# Udoo_Shield.net
KiCad netlist of a schematic drawn in EAGLE
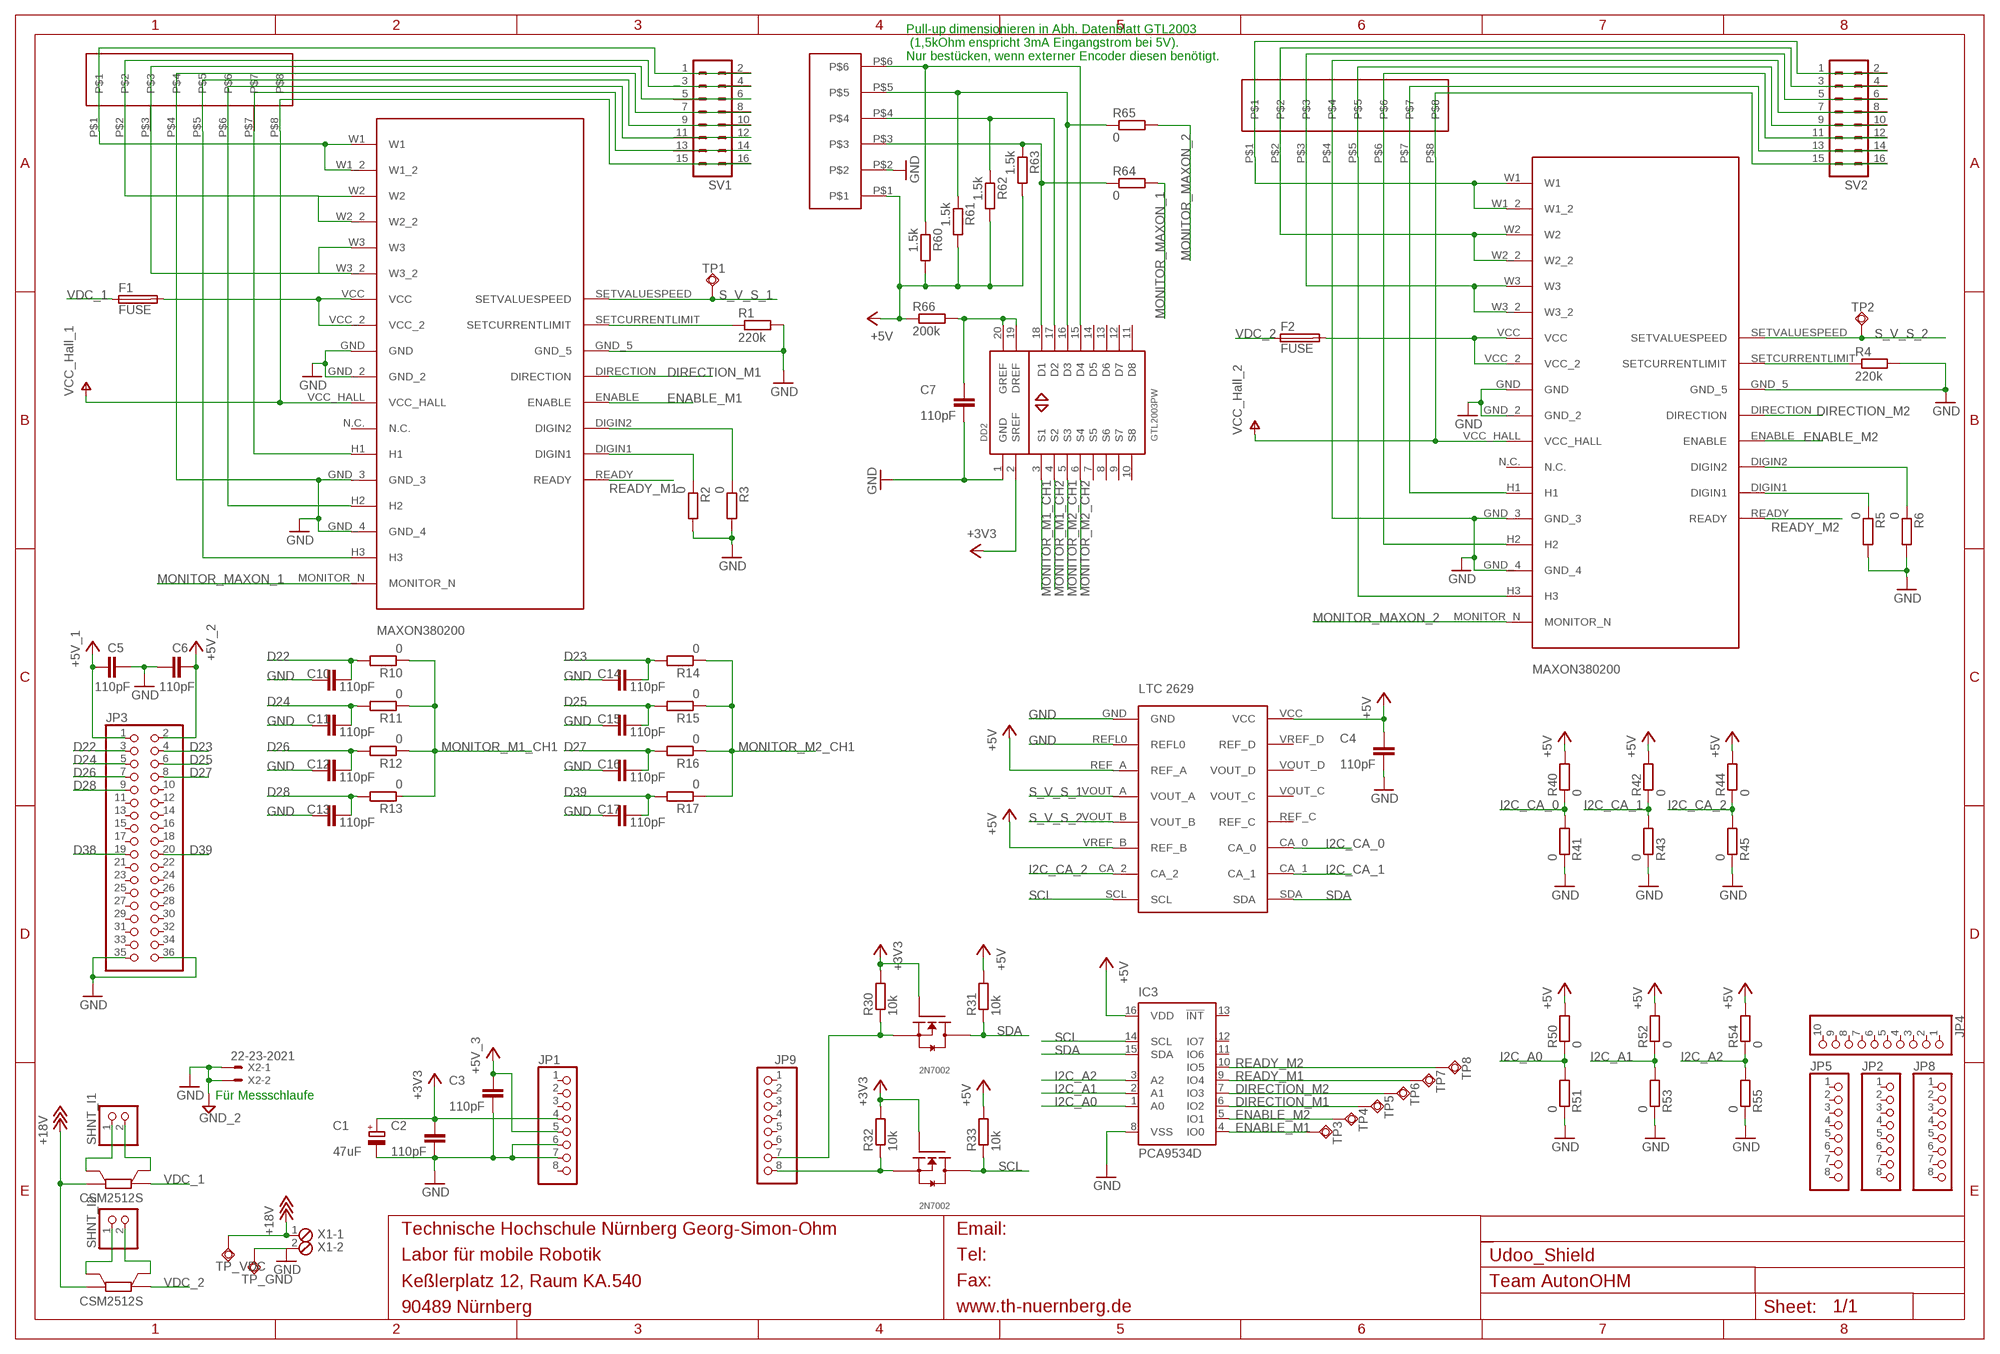
[diagram p0: schematic, sheet 1]

(export (version "E")
  (design (tool "Eeschema 10.0.6"))
  (components
    (comp (ref "C1")
      (value "47uF")
      (footprint "eagle-import:PANASONIC_F")
      (libsource (lib "eagle-import") (part "PANASONI_F_FP"))
    )
    (comp (ref "C2")
      (value "110pF")
      (footprint "eagle-import:SMD-0805")
      (libsource (lib "eagle-import") (part "C-EU0805"))
    )
    (comp (ref "C3")
      (value "110pF")
      (footprint "eagle-import:SMD-0805")
      (libsource (lib "eagle-import") (part "C-EU0805"))
    )
    (comp (ref "C4")
      (value "110pF")
      (footprint "eagle-import:SMD-0805")
      (libsource (lib "eagle-import") (part "C-EU0805"))
    )
    (comp (ref "C5")
      (value "110pF")
      (footprint "eagle-import:SMD-0805")
      (libsource (lib "eagle-import") (part "C-EU0805"))
    )
    (comp (ref "C6")
      (value "110pF")
      (footprint "eagle-import:SMD-0805")
      (libsource (lib "eagle-import") (part "C-EU0805"))
    )
    (comp (ref "C7")
      (value "110pF")
      (footprint "eagle-import:SMD-0805")
      (libsource (lib "eagle-import") (part "C-EU0805"))
    )
    (comp (ref "C10")
      (value "110pF")
      (footprint "eagle-import:SMD-0805")
      (libsource (lib "eagle-import") (part "C-EU0805"))
    )
    (comp (ref "C11")
      (value "110pF")
      (footprint "eagle-import:SMD-0805")
      (libsource (lib "eagle-import") (part "C-EU0805"))
    )
    (comp (ref "C12")
      (value "110pF")
      (footprint "eagle-import:SMD-0805")
      (libsource (lib "eagle-import") (part "C-EU0805"))
    )
    (comp (ref "C13")
      (value "110pF")
      (footprint "eagle-import:SMD-0805")
      (libsource (lib "eagle-import") (part "C-EU0805"))
    )
    (comp (ref "C14")
      (value "110pF")
      (footprint "eagle-import:SMD-0805")
      (libsource (lib "eagle-import") (part "C-EU0805"))
    )
    (comp (ref "C15")
      (value "110pF")
      (footprint "eagle-import:SMD-0805")
      (libsource (lib "eagle-import") (part "C-EU0805"))
    )
    (comp (ref "C16")
      (value "110pF")
      (footprint "eagle-import:SMD-0805")
      (libsource (lib "eagle-import") (part "C-EU0805"))
    )
    (comp (ref "C17")
      (value "110pF")
      (footprint "eagle-import:SMD-0805")
      (libsource (lib "eagle-import") (part "C-EU0805"))
    )
    (comp (ref "DD2")
      (value "GTL2003PW")
      (footprint "eagle-import:TSSOP20")
      (libsource (lib "eagle-import") (part "GTL2003PW"))
    )
    (comp (ref "ENCODER")
      (value "WAGO_PICOMAX_35_6POLIG")
      (footprint "eagle-import:WAGO_PICOMAX_35_6POLIG")
      (libsource (lib "eagle-import") (part "WAGO_PICOMAX_35_6POLIG"))
    )
    (comp (ref "F1")
      (value "FUSE")
      (footprint "eagle-import:FUSE")
      (libsource (lib "eagle-import") (part "FUSE"))
    )
    (comp (ref "F2")
      (value "FUSE")
      (footprint "eagle-import:FUSE")
      (libsource (lib "eagle-import") (part "FUSE"))
    )
    (comp (ref "FRAME1")
      (value "A3L-LOC")
      (footprint "eagle-import:A3L-LOC")
      (fields
        (field (name "AUTHOR") "Team AutonOHM")
        (field (name "PROJECT_NAME") "MaxonShield")
        (field (name "EMAIL") "stefan.may@th-nuernberg.de")
      )
      (libsource (lib "eagle-import") (part "A3L-LOC"))
    )
    (comp (ref "IC3")
      (value "PCA9534D")
      (footprint "eagle-import:SO16W")
      (fields (field (name "MPN") "PCA9534DB"))
      (libsource (lib "eagle-import") (part "PCA9534D"))
    )
    (comp (ref "JP1")
      (value "PINHD-1X8")
      (footprint "eagle-import:1X08")
      (libsource (lib "eagle-import") (part "PINHD-1X8"))
    )
    (comp (ref "JP2")
      (value "PINHD-1X8")
      (footprint "eagle-import:1X08")
      (libsource (lib "eagle-import") (part "PINHD-1X8"))
    )
    (comp (ref "JP3")
      (value "PINHD-2X18")
      (footprint "eagle-import:2X18")
      (libsource (lib "eagle-import") (part "PINHD-2X18"))
    )
    (comp (ref "JP4")
      (value "PINHD-1X10")
      (footprint "eagle-import:1X10")
      (libsource (lib "eagle-import") (part "PINHD-1X10"))
    )
    (comp (ref "JP5")
      (value "PINHD-1X8")
      (footprint "eagle-import:1X08")
      (libsource (lib "eagle-import") (part "PINHD-1X8"))
    )
    (comp (ref "JP8")
      (value "PINHD-1X8")
      (footprint "eagle-import:1X08")
      (libsource (lib "eagle-import") (part "PINHD-1X8"))
    )
    (comp (ref "JP9")
      (value "PINHD-1X8")
      (footprint "eagle-import:1X08")
      (libsource (lib "eagle-import") (part "PINHD-1X8"))
    )
    (comp (ref "R1")
      (value "220k")
      (footprint "eagle-import:M1206")
      (libsource (lib "eagle-import") (part "R-EU_M1206"))
    )
    (comp (ref "R2")
      (value "0")
      (footprint "eagle-import:M0805")
      (libsource (lib "eagle-import") (part "R-EU_M0805"))
    )
    (comp (ref "R3")
      (value "0")
      (footprint "eagle-import:M0805")
      (libsource (lib "eagle-import") (part "R-EU_M0805"))
    )
    (comp (ref "R4")
      (value "220k")
      (footprint "eagle-import:M1206")
      (libsource (lib "eagle-import") (part "R-EU_M1206"))
    )
    (comp (ref "R5")
      (value "0")
      (footprint "eagle-import:M0805")
      (libsource (lib "eagle-import") (part "R-EU_M0805"))
    )
    (comp (ref "R6")
      (value "0")
      (footprint "eagle-import:M0805")
      (libsource (lib "eagle-import") (part "R-EU_M0805"))
    )
    (comp (ref "R10")
      (value "0")
      (footprint "eagle-import:M0805")
      (libsource (lib "eagle-import") (part "R-EU_M0805"))
    )
    (comp (ref "R11")
      (value "0")
      (footprint "eagle-import:M0805")
      (libsource (lib "eagle-import") (part "R-EU_M0805"))
    )
    (comp (ref "R12")
      (value "0")
      (footprint "eagle-import:M0805")
      (libsource (lib "eagle-import") (part "R-EU_M0805"))
    )
    (comp (ref "R13")
      (value "0")
      (footprint "eagle-import:M0805")
      (libsource (lib "eagle-import") (part "R-EU_M0805"))
    )
    (comp (ref "R14")
      (value "0")
      (footprint "eagle-import:M0805")
      (libsource (lib "eagle-import") (part "R-EU_M0805"))
    )
    (comp (ref "R15")
      (value "0")
      (footprint "eagle-import:M0805")
      (libsource (lib "eagle-import") (part "R-EU_M0805"))
    )
    (comp (ref "R16")
      (value "0")
      (footprint "eagle-import:M0805")
      (libsource (lib "eagle-import") (part "R-EU_M0805"))
    )
    (comp (ref "R17")
      (value "0")
      (footprint "eagle-import:M0805")
      (libsource (lib "eagle-import") (part "R-EU_M0805"))
    )
    (comp (ref "R30")
      (value "10k")
      (footprint "eagle-import:M0805")
      (libsource (lib "eagle-import") (part "R-EU_M0805"))
    )
    (comp (ref "R31")
      (value "10k")
      (footprint "eagle-import:M0805")
      (libsource (lib "eagle-import") (part "R-EU_M0805"))
    )
    (comp (ref "R32")
      (value "10k")
      (footprint "eagle-import:M0805")
      (libsource (lib "eagle-import") (part "R-EU_M0805"))
    )
    (comp (ref "R33")
      (value "10k")
      (footprint "eagle-import:M0805")
      (libsource (lib "eagle-import") (part "R-EU_M0805"))
    )
    (comp (ref "R40")
      (value "0")
      (footprint "eagle-import:M0805")
      (libsource (lib "eagle-import") (part "R-EU_M0805"))
    )
    (comp (ref "R41")
      (value "0")
      (footprint "eagle-import:M0805")
      (libsource (lib "eagle-import") (part "R-EU_M0805"))
    )
    (comp (ref "R42")
      (value "0")
      (footprint "eagle-import:M0805")
      (libsource (lib "eagle-import") (part "R-EU_M0805"))
    )
    (comp (ref "R43")
      (value "0")
      (footprint "eagle-import:M0805")
      (libsource (lib "eagle-import") (part "R-EU_M0805"))
    )
    (comp (ref "R44")
      (value "0")
      (footprint "eagle-import:M0805")
      (libsource (lib "eagle-import") (part "R-EU_M0805"))
    )
    (comp (ref "R45")
      (value "0")
      (footprint "eagle-import:M0805")
      (libsource (lib "eagle-import") (part "R-EU_M0805"))
    )
    (comp (ref "R50")
      (value "0")
      (footprint "eagle-import:M0805")
      (libsource (lib "eagle-import") (part "R-EU_M0805"))
    )
    (comp (ref "R51")
      (value "0")
      (footprint "eagle-import:M0805")
      (libsource (lib "eagle-import") (part "R-EU_M0805"))
    )
    (comp (ref "R52")
      (value "0")
      (footprint "eagle-import:M0805")
      (libsource (lib "eagle-import") (part "R-EU_M0805"))
    )
    (comp (ref "R53")
      (value "0")
      (footprint "eagle-import:M0805")
      (libsource (lib "eagle-import") (part "R-EU_M0805"))
    )
    (comp (ref "R54")
      (value "0")
      (footprint "eagle-import:M0805")
      (libsource (lib "eagle-import") (part "R-EU_M0805"))
    )
    (comp (ref "R55")
      (value "0")
      (footprint "eagle-import:M0805")
      (libsource (lib "eagle-import") (part "R-EU_M0805"))
    )
    (comp (ref "R60")
      (value "1.5k")
      (footprint "eagle-import:M0805")
      (libsource (lib "eagle-import") (part "R-EU_M0805"))
    )
    (comp (ref "R61")
      (value "1.5k")
      (footprint "eagle-import:M0805")
      (libsource (lib "eagle-import") (part "R-EU_M0805"))
    )
    (comp (ref "R62")
      (value "1.5k")
      (footprint "eagle-import:M0805")
      (libsource (lib "eagle-import") (part "R-EU_M0805"))
    )
    (comp (ref "R63")
      (value "1.5k")
      (footprint "eagle-import:M0805")
      (libsource (lib "eagle-import") (part "R-EU_M0805"))
    )
    (comp (ref "R64")
      (value "0")
      (footprint "eagle-import:M0805")
      (libsource (lib "eagle-import") (part "R-EU_M0805"))
    )
    (comp (ref "R65")
      (value "0")
      (footprint "eagle-import:M0805")
      (libsource (lib "eagle-import") (part "R-EU_M0805"))
    )
    (comp (ref "R66")
      (value "200k")
      (footprint "eagle-import:M0805")
      (libsource (lib "eagle-import") (part "R-EU_M0805"))
    )
    (comp (ref "SHNT_I1")
      (value "PINHD-1X2")
      (footprint "eagle-import:1X02")
      (libsource (lib "eagle-import") (part "PINHD-1X2"))
    )
    (comp (ref "SHNT_I2")
      (value "PINHD-1X2")
      (footprint "eagle-import:1X02")
      (libsource (lib "eagle-import") (part "PINHD-1X2"))
    )
    (comp (ref "SV1")
      (value "MA08-2")
      (footprint "eagle-import:MA08-2")
      (libsource (lib "eagle-import") (part "MA08-2"))
    )
    (comp (ref "SV2")
      (value "MA08-2")
      (footprint "eagle-import:MA08-2")
      (libsource (lib "eagle-import") (part "MA08-2"))
    )
    (comp (ref "TP1")
      (value "TPSQB1,27")
      (footprint "eagle-import:B1,27")
      (libsource (lib "eagle-import") (part "TPSQB1,27"))
    )
    (comp (ref "TP2")
      (value "TPSQB1,27")
      (footprint "eagle-import:B1,27")
      (libsource (lib "eagle-import") (part "TPSQB1,27"))
    )
    (comp (ref "TP3")
      (value "TPSQB1,27")
      (footprint "eagle-import:B1,27")
      (libsource (lib "eagle-import") (part "TPSQB1,27"))
    )
    (comp (ref "TP4")
      (value "TPSQB1,27")
      (footprint "eagle-import:B1,27")
      (libsource (lib "eagle-import") (part "TPSQB1,27"))
    )
    (comp (ref "TP5")
      (value "TPSQB1,27")
      (footprint "eagle-import:B1,27")
      (libsource (lib "eagle-import") (part "TPSQB1,27"))
    )
    (comp (ref "TP6")
      (value "TPSQB1,27")
      (footprint "eagle-import:B1,27")
      (libsource (lib "eagle-import") (part "TPSQB1,27"))
    )
    (comp (ref "TP7")
      (value "TPSQB1,27")
      (footprint "eagle-import:B1,27")
      (libsource (lib "eagle-import") (part "TPSQB1,27"))
    )
    (comp (ref "TP8")
      (value "TPSQB1,27")
      (footprint "eagle-import:B1,27")
      (libsource (lib "eagle-import") (part "TPSQB1,27"))
    )
    (comp (ref "TP_GND")
      (value "TPSQB1,27")
      (footprint "eagle-import:B1,27")
      (libsource (lib "eagle-import") (part "TPSQB1,27"))
    )
    (comp (ref "TP_VDC")
      (value "TPSQB1,27")
      (footprint "eagle-import:B1,27")
      (libsource (lib "eagle-import") (part "TPSQB1,27"))
    )
    (comp (ref "U$1")
      (value "MAXON380200")
      (footprint "eagle-import:380200")
      (libsource (lib "eagle-import") (part "MAXON380200"))
    )
    (comp (ref "U$2")
      (value "MAXON380200")
      (footprint "eagle-import:380200")
      (libsource (lib "eagle-import") (part "MAXON380200"))
    )
    (comp (ref "U$3")
      (value "WAGO_PICOMAX_35_8POLIG")
      (footprint "eagle-import:WAGO_PICOMAX_35_8POLIG")
      (libsource (lib "eagle-import") (part "WAGO_PICOMAX_35_8POLIG"))
    )
    (comp (ref "U$4")
      (value "WAGO_PICOMAX_35_8POLIG")
      (footprint "eagle-import:WAGO_PICOMAX_35_8POLIG")
      (libsource (lib "eagle-import") (part "WAGO_PICOMAX_35_8POLIG"))
    )
    (comp (ref "U$5")
      (value "LTC2629")
      (footprint "eagle-import:LTC2629")
      (libsource (lib "eagle-import") (part "LTC2629"))
    )
    (comp (ref "U$6")
      (value "N-CH_MOSFET_2N7002")
      (footprint "eagle-import:2N7002")
      (libsource (lib "eagle-import") (part "N-CH_MOSFET_2N7002"))
    )
    (comp (ref "U$10")
      (value "CSM2512S")
      (footprint "eagle-import:CSM2512S")
      (libsource (lib "eagle-import") (part "CSM2512S"))
    )
    (comp (ref "U$14")
      (value "CSM2512S")
      (footprint "eagle-import:CSM2512S")
      (libsource (lib "eagle-import") (part "CSM2512S"))
    )
    (comp (ref "U$15")
      (value "N-CH_MOSFET_2N7002")
      (footprint "eagle-import:2N7002")
      (libsource (lib "eagle-import") (part "N-CH_MOSFET_2N7002"))
    )
    (comp (ref "X1")
      (value "MPT2")
      (footprint "eagle-import:2POL254")
      (libsource (lib "eagle-import") (part "MPT2"))
    )
    (comp (ref "X2")
      (value "22-23-2021")
      (footprint "eagle-import:22-23-2021")
      (fields (field (name "MF") "MOLEX"))
      (libsource (lib "eagle-import") (part "22-23-2021"))
    )
  )
  (nets
    (net (code "1") (name "+3V3") (class "Default")
      (node (ref "C1") (pin "+") (pinfunction "+_+") (pintype "passive"))
      (node (ref "C2") (pin "1") (pinfunction "1_1") (pintype "passive"))
      (node (ref "DD2") (pin "2") (pinfunction "SREF_2") (pintype "input"))
      (node (ref "JP1") (pin "4") (pinfunction "4_4") (pintype "passive"))
      (node (ref "R30") (pin "2") (pinfunction "2_2") (pintype "passive"))
      (node (ref "R32") (pin "2") (pinfunction "2_2") (pintype "passive"))
      (node (ref "U$15") (pin "GATE") (pinfunction "G_GATE") (pintype "passive"))
      (node (ref "U$6") (pin "GATE") (pinfunction "G_GATE") (pintype "passive"))
    )
    (net (code "2") (name "+5V") (class "Default")
      (node (ref "C3") (pin "1") (pinfunction "1_1") (pintype "passive"))
      (node (ref "C4") (pin "1") (pinfunction "1_1") (pintype "passive"))
      (node (ref "C5") (pin "1") (pinfunction "1_1") (pintype "passive"))
      (node (ref "C6") (pin "2") (pinfunction "2_2") (pintype "passive"))
      (node (ref "ENCODER") (pin "P$1") (pinfunction "P$1_P$1") (pintype "bidirectional"))
      (node (ref "IC3") (pin "16") (pinfunction "VDD_16") (pintype "power_in"))
      (node (ref "JP1") (pin "5") (pinfunction "5_5") (pintype "passive"))
      (node (ref "JP3") (pin "1") (pinfunction "1_1") (pintype "passive"))
      (node (ref "JP3") (pin "2") (pinfunction "2_2") (pintype "passive"))
      (node (ref "R31") (pin "2") (pinfunction "2_2") (pintype "passive"))
      (node (ref "R33") (pin "2") (pinfunction "2_2") (pintype "passive"))
      (node (ref "R40") (pin "2") (pinfunction "2_2") (pintype "passive"))
      (node (ref "R42") (pin "2") (pinfunction "2_2") (pintype "passive"))
      (node (ref "R44") (pin "2") (pinfunction "2_2") (pintype "passive"))
      (node (ref "R50") (pin "2") (pinfunction "2_2") (pintype "passive"))
      (node (ref "R52") (pin "2") (pinfunction "2_2") (pintype "passive"))
      (node (ref "R54") (pin "2") (pinfunction "2_2") (pintype "passive"))
      (node (ref "R60") (pin "2") (pinfunction "2_2") (pintype "passive"))
      (node (ref "R61") (pin "2") (pinfunction "2_2") (pintype "passive"))
      (node (ref "R62") (pin "2") (pinfunction "2_2") (pintype "passive"))
      (node (ref "R63") (pin "2") (pinfunction "2_2") (pintype "passive"))
      (node (ref "R66") (pin "1") (pinfunction "1_1") (pintype "passive"))
      (node (ref "U$5") (pin "REF_A") (pinfunction "REF_A_REF_A") (pintype "bidirectional"))
      (node (ref "U$5") (pin "VCC") (pinfunction "VCC_VCC") (pintype "bidirectional"))
      (node (ref "U$5") (pin "VREF_B") (pinfunction "REF_B_VREF_B") (pintype "bidirectional"))
    )
    (net (code "3") (name "+18V") (class "Default")
      (node (ref "TP_VDC") (pin "TP") (pinfunction "TP_TP") (pintype "input"))
      (node (ref "U$10") (pin "I_2") (pinfunction "I_2_I_2") (pintype "passive"))
      (node (ref "U$14") (pin "I_2") (pinfunction "I_2_I_2") (pintype "passive"))
      (node (ref "X1") (pin "1") (pinfunction "1_1") (pintype "passive"))
    )
    (net (code "4") (name "/D22") (class "Default")
      (node (ref "C10") (pin "2") (pinfunction "2_2") (pintype "passive"))
      (node (ref "JP3") (pin "3") (pinfunction "3_3") (pintype "passive"))
      (node (ref "R10") (pin "2") (pinfunction "2_2") (pintype "passive"))
    )
    (net (code "5") (name "/D23") (class "Default")
      (node (ref "C14") (pin "2") (pinfunction "2_2") (pintype "passive"))
      (node (ref "JP3") (pin "4") (pinfunction "4_4") (pintype "passive"))
      (node (ref "R14") (pin "2") (pinfunction "2_2") (pintype "passive"))
    )
    (net (code "6") (name "/D24") (class "Default")
      (node (ref "C11") (pin "2") (pinfunction "2_2") (pintype "passive"))
      (node (ref "JP3") (pin "5") (pinfunction "5_5") (pintype "passive"))
      (node (ref "R11") (pin "2") (pinfunction "2_2") (pintype "passive"))
    )
    (net (code "7") (name "/D25") (class "Default")
      (node (ref "C15") (pin "2") (pinfunction "2_2") (pintype "passive"))
      (node (ref "JP3") (pin "6") (pinfunction "6_6") (pintype "passive"))
      (node (ref "R15") (pin "2") (pinfunction "2_2") (pintype "passive"))
    )
    (net (code "8") (name "/D26") (class "Default")
      (node (ref "C12") (pin "2") (pinfunction "2_2") (pintype "passive"))
      (node (ref "JP3") (pin "7") (pinfunction "7_7") (pintype "passive"))
      (node (ref "R12") (pin "2") (pinfunction "2_2") (pintype "passive"))
    )
    (net (code "9") (name "/D27") (class "Default")
      (node (ref "C16") (pin "2") (pinfunction "2_2") (pintype "passive"))
      (node (ref "JP3") (pin "8") (pinfunction "8_8") (pintype "passive"))
      (node (ref "R16") (pin "2") (pinfunction "2_2") (pintype "passive"))
    )
    (net (code "10") (name "/D28") (class "Default")
      (node (ref "C13") (pin "2") (pinfunction "2_2") (pintype "passive"))
      (node (ref "JP3") (pin "9") (pinfunction "9_9") (pintype "passive"))
      (node (ref "R13") (pin "2") (pinfunction "2_2") (pintype "passive"))
    )
    (net (code "11") (name "/D38") (class "Default")
      (node (ref "JP3") (pin "19") (pinfunction "19_19") (pintype "passive"))
    )
    (net (code "12") (name "/D39") (class "Default")
      (node (ref "C17") (pin "2") (pinfunction "2_2") (pintype "passive"))
      (node (ref "JP3") (pin "20") (pinfunction "20_20") (pintype "passive"))
      (node (ref "R17") (pin "2") (pinfunction "2_2") (pintype "passive"))
    )
    (net (code "13") (name "/DIRECTION_M1") (class "Default")
      (node (ref "IC3") (pin "6") (pinfunction "IO2_6") (pintype "bidirectional"))
      (node (ref "TP5") (pin "TP") (pinfunction "TP_TP") (pintype "input"))
      (node (ref "U$1") (pin "DIRECTION") (pinfunction "DIRECTION_DIRECTION") (pintype "bidirectional"))
    )
    (net (code "14") (name "/DIRECTION_M2") (class "Default")
      (node (ref "IC3") (pin "7") (pinfunction "IO3_7") (pintype "bidirectional"))
      (node (ref "TP6") (pin "TP") (pinfunction "TP_TP") (pintype "input"))
      (node (ref "U$2") (pin "DIRECTION") (pinfunction "DIRECTION_DIRECTION") (pintype "bidirectional"))
    )
    (net (code "15") (name "/ENABLE_M1") (class "Default")
      (node (ref "IC3") (pin "4") (pinfunction "IO0_4") (pintype "bidirectional"))
      (node (ref "TP3") (pin "TP") (pinfunction "TP_TP") (pintype "input"))
      (node (ref "U$1") (pin "ENABLE") (pinfunction "ENABLE_ENABLE") (pintype "bidirectional"))
    )
    (net (code "16") (name "/ENABLE_M2") (class "Default")
      (node (ref "IC3") (pin "5") (pinfunction "IO1_5") (pintype "bidirectional"))
      (node (ref "TP4") (pin "TP") (pinfunction "TP_TP") (pintype "input"))
      (node (ref "U$2") (pin "ENABLE") (pinfunction "ENABLE_ENABLE") (pintype "bidirectional"))
    )
    (net (code "17") (name "/I2C_A0") (class "Default")
      (node (ref "IC3") (pin "1") (pinfunction "A0_1") (pintype "input"))
      (node (ref "R50") (pin "1") (pinfunction "1_1") (pintype "passive"))
      (node (ref "R51") (pin "2") (pinfunction "2_2") (pintype "passive"))
    )
    (net (code "18") (name "/I2C_A1") (class "Default")
      (node (ref "IC3") (pin "2") (pinfunction "A1_2") (pintype "input"))
      (node (ref "R52") (pin "1") (pinfunction "1_1") (pintype "passive"))
      (node (ref "R53") (pin "2") (pinfunction "2_2") (pintype "passive"))
    )
    (net (code "19") (name "/I2C_A2") (class "Default")
      (node (ref "IC3") (pin "3") (pinfunction "A2_3") (pintype "input"))
      (node (ref "R54") (pin "1") (pinfunction "1_1") (pintype "passive"))
      (node (ref "R55") (pin "2") (pinfunction "2_2") (pintype "passive"))
    )
    (net (code "20") (name "/I2C_CA_0") (class "Default")
      (node (ref "R40") (pin "1") (pinfunction "1_1") (pintype "passive"))
      (node (ref "R41") (pin "2") (pinfunction "2_2") (pintype "passive"))
      (node (ref "U$5") (pin "CA_0") (pinfunction "CA_0_CA_0") (pintype "bidirectional"))
    )
    (net (code "21") (name "/I2C_CA_1") (class "Default")
      (node (ref "R42") (pin "1") (pinfunction "1_1") (pintype "passive"))
      (node (ref "R43") (pin "2") (pinfunction "2_2") (pintype "passive"))
      (node (ref "U$5") (pin "CA_1") (pinfunction "CA_1_CA_1") (pintype "bidirectional"))
    )
    (net (code "22") (name "/I2C_CA_2") (class "Default")
      (node (ref "R44") (pin "1") (pinfunction "1_1") (pintype "passive"))
      (node (ref "R45") (pin "2") (pinfunction "2_2") (pintype "passive"))
      (node (ref "U$5") (pin "CA_2") (pinfunction "CA_2_CA_2") (pintype "bidirectional"))
    )
    (net (code "23") (name "/MONITOR_M1_CH1") (class "Default")
      (node (ref "DD2") (pin "3") (pinfunction "S1_3") (pintype "bidirectional"))
      (node (ref "R10") (pin "1") (pinfunction "1_1") (pintype "passive"))
      (node (ref "R11") (pin "1") (pinfunction "1_1") (pintype "passive"))
      (node (ref "R12") (pin "1") (pinfunction "1_1") (pintype "passive"))
      (node (ref "R13") (pin "1") (pinfunction "1_1") (pintype "passive"))
    )
    (net (code "24") (name "/MONITOR_M1_CH2") (class "Default")
      (node (ref "DD2") (pin "4") (pinfunction "S2_4") (pintype "bidirectional"))
    )
    (net (code "25") (name "/MONITOR_M2_CH1") (class "Default")
      (node (ref "DD2") (pin "5") (pinfunction "S3_5") (pintype "bidirectional"))
      (node (ref "R14") (pin "1") (pinfunction "1_1") (pintype "passive"))
      (node (ref "R15") (pin "1") (pinfunction "1_1") (pintype "passive"))
      (node (ref "R16") (pin "1") (pinfunction "1_1") (pintype "passive"))
      (node (ref "R17") (pin "1") (pinfunction "1_1") (pintype "passive"))
    )
    (net (code "26") (name "/MONITOR_M2_CH2") (class "Default")
      (node (ref "DD2") (pin "6") (pinfunction "S4_6") (pintype "bidirectional"))
    )
    (net (code "27") (name "/MONITOR_MAXON_1") (class "Default")
      (node (ref "R64") (pin "2") (pinfunction "2_2") (pintype "passive"))
      (node (ref "U$1") (pin "MONITOR_N") (pinfunction "MONITOR_N_MONITOR_N") (pintype "bidirectional"))
    )
    (net (code "28") (name "/MONITOR_MAXON_2") (class "Default")
      (node (ref "R65") (pin "2") (pinfunction "2_2") (pintype "passive"))
      (node (ref "U$2") (pin "MONITOR_N") (pinfunction "MONITOR_N_MONITOR_N") (pintype "bidirectional"))
    )
    (net (code "29") (name "/READY_M1") (class "Default")
      (node (ref "IC3") (pin "9") (pinfunction "IO4_9") (pintype "bidirectional"))
      (node (ref "TP7") (pin "TP") (pinfunction "TP_TP") (pintype "input"))
      (node (ref "U$1") (pin "READY") (pinfunction "READY_READY") (pintype "bidirectional"))
    )
    (net (code "30") (name "/READY_M2") (class "Default")
      (node (ref "IC3") (pin "10") (pinfunction "IO5_10") (pintype "bidirectional"))
      (node (ref "TP8") (pin "TP") (pinfunction "TP_TP") (pintype "input"))
      (node (ref "U$2") (pin "READY") (pinfunction "READY_READY") (pintype "bidirectional"))
    )
    (net (code "31") (name "/SCL") (class "Default")
      (node (ref "IC3") (pin "14") (pinfunction "SCL_14") (pintype "input"))
      (node (ref "R33") (pin "1") (pinfunction "1_1") (pintype "passive"))
      (node (ref "U$5") (pin "SCL") (pinfunction "SCL_SCL") (pintype "bidirectional"))
      (node (ref "U$6") (pin "DRAIN") (pinfunction "D_DRAIN") (pintype "passive"))
    )
    (net (code "32") (name "/SDA") (class "Default")
      (node (ref "IC3") (pin "15") (pinfunction "SDA_15") (pintype "bidirectional"))
      (node (ref "R31") (pin "1") (pinfunction "1_1") (pintype "passive"))
      (node (ref "U$15") (pin "DRAIN") (pinfunction "D_DRAIN") (pintype "passive"))
      (node (ref "U$5") (pin "SDA") (pinfunction "SDA_SDA") (pintype "bidirectional"))
    )
    (net (code "33") (name "/S_V_S_1") (class "Default")
      (node (ref "TP1") (pin "TP") (pinfunction "TP_TP") (pintype "input"))
      (node (ref "U$1") (pin "SETVALUESPEED") (pinfunction "SETVALUESPEED_SETVALUESPEED") (pintype "bidirectional"))
      (node (ref "U$5") (pin "VOUT_A") (pinfunction "VOUT_A_VOUT_A") (pintype "bidirectional"))
    )
    (net (code "34") (name "/S_V_S_2") (class "Default")
      (node (ref "TP2") (pin "TP") (pinfunction "TP_TP") (pintype "input"))
      (node (ref "U$2") (pin "SETVALUESPEED") (pinfunction "SETVALUESPEED_SETVALUESPEED") (pintype "bidirectional"))
      (node (ref "U$5") (pin "VOUT_B") (pinfunction "VOUT_B_VOUT_B") (pintype "bidirectional"))
    )
    (net (code "35") (name "/VDC_1") (class "Default")
      (node (ref "F1") (pin "P$1") (pinfunction "1_P$1") (pintype "passive"))
      (node (ref "U$10") (pin "I_1") (pinfunction "I_1_I_1") (pintype "passive"))
    )
    (net (code "36") (name "/VDC_2") (class "Default")
      (node (ref "F2") (pin "P$1") (pinfunction "1_P$1") (pintype "passive"))
      (node (ref "U$14") (pin "I_1") (pinfunction "I_1_I_1") (pintype "passive"))
    )
    (net (code "37") (name "GND") (class "Default")
      (node (ref "C1") (pin "-") (pinfunction "-_-") (pintype "passive"))
      (node (ref "C10") (pin "1") (pinfunction "1_1") (pintype "passive"))
      (node (ref "C11") (pin "1") (pinfunction "1_1") (pintype "passive"))
      (node (ref "C12") (pin "1") (pinfunction "1_1") (pintype "passive"))
      (node (ref "C13") (pin "1") (pinfunction "1_1") (pintype "passive"))
      (node (ref "C14") (pin "1") (pinfunction "1_1") (pintype "passive"))
      (node (ref "C15") (pin "1") (pinfunction "1_1") (pintype "passive"))
      (node (ref "C16") (pin "1") (pinfunction "1_1") (pintype "passive"))
      (node (ref "C17") (pin "1") (pinfunction "1_1") (pintype "passive"))
      (node (ref "C2") (pin "2") (pinfunction "2_2") (pintype "passive"))
      (node (ref "C3") (pin "2") (pinfunction "2_2") (pintype "passive"))
      (node (ref "C4") (pin "2") (pinfunction "2_2") (pintype "passive"))
      (node (ref "C5") (pin "2") (pinfunction "2_2") (pintype "passive"))
      (node (ref "C6") (pin "1") (pinfunction "1_1") (pintype "passive"))
      (node (ref "C7") (pin "2") (pinfunction "2_2") (pintype "passive"))
      (node (ref "DD2") (pin "1") (pinfunction "GND_1") (pintype "power_in"))
      (node (ref "ENCODER") (pin "P$2") (pinfunction "P$2_P$2") (pintype "bidirectional"))
      (node (ref "IC3") (pin "8") (pinfunction "VSS_8") (pintype "power_in"))
      (node (ref "JP1") (pin "6") (pinfunction "6_6") (pintype "passive"))
      (node (ref "JP1") (pin "7") (pinfunction "7_7") (pintype "passive"))
      (node (ref "JP3") (pin "35") (pinfunction "35_35") (pintype "passive"))
      (node (ref "JP3") (pin "36") (pinfunction "36_36") (pintype "passive"))
      (node (ref "R1") (pin "2") (pinfunction "2_2") (pintype "passive"))
      (node (ref "R2") (pin "2") (pinfunction "2_2") (pintype "passive"))
      (node (ref "R3") (pin "2") (pinfunction "2_2") (pintype "passive"))
      (node (ref "R4") (pin "2") (pinfunction "2_2") (pintype "passive"))
      (node (ref "R41") (pin "1") (pinfunction "1_1") (pintype "passive"))
      (node (ref "R43") (pin "1") (pinfunction "1_1") (pintype "passive"))
      (node (ref "R45") (pin "1") (pinfunction "1_1") (pintype "passive"))
      (node (ref "R5") (pin "2") (pinfunction "2_2") (pintype "passive"))
      (node (ref "R51") (pin "1") (pinfunction "1_1") (pintype "passive"))
      (node (ref "R53") (pin "1") (pinfunction "1_1") (pintype "passive"))
      (node (ref "R55") (pin "1") (pinfunction "1_1") (pintype "passive"))
      (node (ref "R6") (pin "2") (pinfunction "2_2") (pintype "passive"))
      (node (ref "SV1") (pin "7") (pinfunction "7_7") (pintype "passive"))
      (node (ref "SV1") (pin "8") (pinfunction "8_8") (pintype "passive"))
      (node (ref "SV2") (pin "7") (pinfunction "7_7") (pintype "passive"))
      (node (ref "SV2") (pin "8") (pinfunction "8_8") (pintype "passive"))
      (node (ref "TP_GND") (pin "TP") (pinfunction "TP_TP") (pintype "input"))
      (node (ref "U$1") (pin "GND") (pinfunction "GND_GND") (pintype "bidirectional"))
      (node (ref "U$1") (pin "GND_2") (pinfunction "GND_2_GND_2") (pintype "bidirectional"))
      (node (ref "U$1") (pin "GND_3") (pinfunction "GND_3_GND_3") (pintype "bidirectional"))
      (node (ref "U$1") (pin "GND_4") (pinfunction "GND_4_GND_4") (pintype "bidirectional"))
      (node (ref "U$1") (pin "GND_5") (pinfunction "GND_5_GND_5") (pintype "bidirectional"))
      (node (ref "U$2") (pin "GND") (pinfunction "GND_GND") (pintype "bidirectional"))
      (node (ref "U$2") (pin "GND_2") (pinfunction "GND_2_GND_2") (pintype "bidirectional"))
      (node (ref "U$2") (pin "GND_3") (pinfunction "GND_3_GND_3") (pintype "bidirectional"))
      (node (ref "U$2") (pin "GND_4") (pinfunction "GND_4_GND_4") (pintype "bidirectional"))
      (node (ref "U$2") (pin "GND_5") (pinfunction "GND_5_GND_5") (pintype "bidirectional"))
      (node (ref "U$3") (pin "P$4") (pinfunction "P$4_P$4") (pintype "bidirectional"))
      (node (ref "U$4") (pin "P$4") (pinfunction "P$4_P$4") (pintype "bidirectional"))
      (node (ref "U$5") (pin "GND") (pinfunction "GND_GND") (pintype "bidirectional"))
      (node (ref "U$5") (pin "REFL0") (pinfunction "REFL0_REFL0") (pintype "bidirectional"))
      (node (ref "X1") (pin "2") (pinfunction "1_2") (pintype "passive"))
      (node (ref "X2") (pin "1") (pinfunction "S_1") (pintype "passive"))
      (node (ref "X2") (pin "2") (pinfunction "S_2") (pintype "passive"))
    )
    (net (code "38") (name "Net-(DD2-D1)") (class "Default")
      (node (ref "DD2") (pin "18") (pinfunction "D1_18") (pintype "bidirectional"))
      (node (ref "ENCODER") (pin "P$3") (pinfunction "P$3_P$3") (pintype "bidirectional"))
      (node (ref "R63") (pin "1") (pinfunction "1_1") (pintype "passive"))
      (node (ref "R64") (pin "1") (pinfunction "1_1") (pintype "passive"))
    )
    (net (code "39") (name "Net-(DD2-D2)") (class "Default")
      (node (ref "DD2") (pin "17") (pinfunction "D2_17") (pintype "bidirectional"))
      (node (ref "ENCODER") (pin "P$4") (pinfunction "P$4_P$4") (pintype "bidirectional"))
      (node (ref "R62") (pin "1") (pinfunction "1_1") (pintype "passive"))
    )
    (net (code "40") (name "Net-(DD2-D3)") (class "Default")
      (node (ref "DD2") (pin "16") (pinfunction "D3_16") (pintype "bidirectional"))
      (node (ref "ENCODER") (pin "P$5") (pinfunction "P$5_P$5") (pintype "bidirectional"))
      (node (ref "R61") (pin "1") (pinfunction "1_1") (pintype "passive"))
      (node (ref "R65") (pin "1") (pinfunction "1_1") (pintype "passive"))
    )
    (net (code "41") (name "Net-(DD2-D4)") (class "Default")
      (node (ref "DD2") (pin "15") (pinfunction "D4_15") (pintype "bidirectional"))
      (node (ref "ENCODER") (pin "P$6") (pinfunction "P$6_P$6") (pintype "bidirectional"))
      (node (ref "R60") (pin "1") (pinfunction "1_1") (pintype "passive"))
    )
    (net (code "42") (name "Net-(DD2-DREF)") (class "Default")
      (node (ref "C7") (pin "1") (pinfunction "1_1") (pintype "passive"))
      (node (ref "DD2") (pin "19") (pinfunction "DREF_19") (pintype "input"))
      (node (ref "DD2") (pin "20") (pinfunction "GREF_20") (pintype "input"))
      (node (ref "R66") (pin "2") (pinfunction "2_2") (pintype "passive"))
    )
    (net (code "43") (name "Net-(F1-2)") (class "Default")
      (node (ref "F1") (pin "P$2") (pinfunction "2_P$2") (pintype "passive"))
      (node (ref "U$1") (pin "VCC") (pinfunction "VCC_VCC") (pintype "bidirectional"))
      (node (ref "U$1") (pin "VCC_2") (pinfunction "VCC_2_VCC_2") (pintype "bidirectional"))
    )
    (net (code "44") (name "Net-(F2-2)") (class "Default")
      (node (ref "F2") (pin "P$2") (pinfunction "2_P$2") (pintype "passive"))
      (node (ref "U$2") (pin "VCC") (pinfunction "VCC_VCC") (pintype "bidirectional"))
      (node (ref "U$2") (pin "VCC_2") (pinfunction "VCC_2_VCC_2") (pintype "bidirectional"))
    )
    (net (code "45") (name "Net-(R1-Pad1)") (class "Default")
      (node (ref "R1") (pin "1") (pinfunction "1_1") (pintype "passive"))
      (node (ref "U$1") (pin "SETCURRENTLIMIT") (pinfunction "SETCURRENTLIMIT_SETCURRENTLIMIT") (pintype "bidirectional"))
    )
    (net (code "46") (name "Net-(R2-Pad1)") (class "Default")
      (node (ref "R2") (pin "1") (pinfunction "1_1") (pintype "passive"))
      (node (ref "U$1") (pin "DIGIN1") (pinfunction "DIGIN1_DIGIN1") (pintype "bidirectional"))
    )
    (net (code "47") (name "Net-(R3-Pad1)") (class "Default")
      (node (ref "R3") (pin "1") (pinfunction "1_1") (pintype "passive"))
      (node (ref "U$1") (pin "DIGIN2") (pinfunction "DIGIN2_DIGIN2") (pintype "bidirectional"))
    )
    (net (code "48") (name "Net-(R4-Pad1)") (class "Default")
      (node (ref "R4") (pin "1") (pinfunction "1_1") (pintype "passive"))
      (node (ref "U$2") (pin "SETCURRENTLIMIT") (pinfunction "SETCURRENTLIMIT_SETCURRENTLIMIT") (pintype "bidirectional"))
    )
    (net (code "49") (name "Net-(R5-Pad1)") (class "Default")
      (node (ref "R5") (pin "1") (pinfunction "1_1") (pintype "passive"))
      (node (ref "U$2") (pin "DIGIN1") (pinfunction "DIGIN1_DIGIN1") (pintype "bidirectional"))
    )
    (net (code "50") (name "Net-(R6-Pad1)") (class "Default")
      (node (ref "R6") (pin "1") (pinfunction "1_1") (pintype "passive"))
      (node (ref "U$2") (pin "DIGIN2") (pinfunction "DIGIN2_DIGIN2") (pintype "bidirectional"))
    )
    (net (code "51") (name "Net-(SHNT_I1-Pad1)") (class "Default")
      (node (ref "SHNT_I1") (pin "1") (pinfunction "1_1") (pintype "passive"))
      (node (ref "U$10") (pin "E_2") (pinfunction "E_2_E_2") (pintype "passive"))
    )
    (net (code "52") (name "Net-(SHNT_I1-Pad2)") (class "Default")
      (node (ref "SHNT_I1") (pin "2") (pinfunction "2_2") (pintype "passive"))
      (node (ref "U$10") (pin "E_1") (pinfunction "E_1_E_1") (pintype "passive"))
    )
    (net (code "53") (name "Net-(SHNT_I2-Pad1)") (class "Default")
      (node (ref "SHNT_I2") (pin "1") (pinfunction "1_1") (pintype "passive"))
      (node (ref "U$14") (pin "E_2") (pinfunction "E_2_E_2") (pintype "passive"))
    )
    (net (code "54") (name "Net-(SHNT_I2-Pad2)") (class "Default")
      (node (ref "SHNT_I2") (pin "2") (pinfunction "2_2") (pintype "passive"))
      (node (ref "U$14") (pin "E_1") (pinfunction "E_1_E_1") (pintype "passive"))
    )
    (net (code "55") (name "Net-(SV1-Pad1)") (class "Default")
      (node (ref "SV1") (pin "1") (pinfunction "1_1") (pintype "passive"))
      (node (ref "SV1") (pin "2") (pinfunction "2_2") (pintype "passive"))
      (node (ref "U$1") (pin "W1") (pinfunction "W1_W1") (pintype "bidirectional"))
      (node (ref "U$1") (pin "W1_2") (pinfunction "W1_2_W1_2") (pintype "bidirectional"))
      (node (ref "U$4") (pin "P$1") (pinfunction "P$1_P$1") (pintype "bidirectional"))
    )
    (net (code "56") (name "Net-(SV1-Pad3)") (class "Default")
      (node (ref "SV1") (pin "3") (pinfunction "3_3") (pintype "passive"))
      (node (ref "SV1") (pin "4") (pinfunction "4_4") (pintype "passive"))
      (node (ref "U$1") (pin "W2") (pinfunction "W2_W2") (pintype "bidirectional"))
      (node (ref "U$1") (pin "W2_2") (pinfunction "W2_2_W2_2") (pintype "bidirectional"))
      (node (ref "U$4") (pin "P$2") (pinfunction "P$2_P$2") (pintype "bidirectional"))
    )
    (net (code "57") (name "Net-(SV1-Pad5)") (class "Default")
      (node (ref "SV1") (pin "5") (pinfunction "5_5") (pintype "passive"))
      (node (ref "SV1") (pin "6") (pinfunction "6_6") (pintype "passive"))
      (node (ref "U$1") (pin "W3") (pinfunction "W3_W3") (pintype "bidirectional"))
      (node (ref "U$1") (pin "W3_2") (pinfunction "W3_2_W3_2") (pintype "bidirectional"))
      (node (ref "U$4") (pin "P$3") (pinfunction "P$3_P$3") (pintype "bidirectional"))
    )
    (net (code "58") (name "Net-(SV1-Pad10)") (class "Default")
      (node (ref "SV1") (pin "10") (pinfunction "10_10") (pintype "passive"))
      (node (ref "SV1") (pin "9") (pinfunction "9_9") (pintype "passive"))
      (node (ref "U$1") (pin "H3") (pinfunction "H3_H3") (pintype "bidirectional"))
      (node (ref "U$4") (pin "P$5") (pinfunction "P$5_P$5") (pintype "bidirectional"))
    )
    (net (code "59") (name "Net-(SV1-Pad11)") (class "Default")
      (node (ref "SV1") (pin "11") (pinfunction "11_11") (pintype "passive"))
      (node (ref "SV1") (pin "12") (pinfunction "12_12") (pintype "passive"))
      (node (ref "U$1") (pin "H2") (pinfunction "H2_H2") (pintype "bidirectional"))
      (node (ref "U$4") (pin "P$6") (pinfunction "P$6_P$6") (pintype "bidirectional"))
    )
    (net (code "60") (name "Net-(SV1-Pad13)") (class "Default")
      (node (ref "SV1") (pin "13") (pinfunction "13_13") (pintype "passive"))
      (node (ref "SV1") (pin "14") (pinfunction "14_14") (pintype "passive"))
      (node (ref "U$1") (pin "H1") (pinfunction "H1_H1") (pintype "bidirectional"))
      (node (ref "U$4") (pin "P$7") (pinfunction "P$7_P$7") (pintype "bidirectional"))
    )
    (net (code "61") (name "Net-(SV2-Pad1)") (class "Default")
      (node (ref "SV2") (pin "1") (pinfunction "1_1") (pintype "passive"))
      (node (ref "SV2") (pin "2") (pinfunction "2_2") (pintype "passive"))
      (node (ref "U$2") (pin "W1") (pinfunction "W1_W1") (pintype "bidirectional"))
      (node (ref "U$2") (pin "W1_2") (pinfunction "W1_2_W1_2") (pintype "bidirectional"))
      (node (ref "U$3") (pin "P$1") (pinfunction "P$1_P$1") (pintype "bidirectional"))
    )
    (net (code "62") (name "Net-(SV2-Pad3)") (class "Default")
      (node (ref "SV2") (pin "3") (pinfunction "3_3") (pintype "passive"))
      (node (ref "SV2") (pin "4") (pinfunction "4_4") (pintype "passive"))
      (node (ref "U$2") (pin "W2") (pinfunction "W2_W2") (pintype "bidirectional"))
      (node (ref "U$2") (pin "W2_2") (pinfunction "W2_2_W2_2") (pintype "bidirectional"))
      (node (ref "U$3") (pin "P$2") (pinfunction "P$2_P$2") (pintype "bidirectional"))
    )
    (net (code "63") (name "Net-(SV2-Pad5)") (class "Default")
      (node (ref "SV2") (pin "5") (pinfunction "5_5") (pintype "passive"))
      (node (ref "SV2") (pin "6") (pinfunction "6_6") (pintype "passive"))
      (node (ref "U$2") (pin "W3") (pinfunction "W3_W3") (pintype "bidirectional"))
      (node (ref "U$2") (pin "W3_2") (pinfunction "W3_2_W3_2") (pintype "bidirectional"))
      (node (ref "U$3") (pin "P$3") (pinfunction "P$3_P$3") (pintype "bidirectional"))
    )
    (net (code "64") (name "Net-(SV2-Pad10)") (class "Default")
      (node (ref "SV2") (pin "10") (pinfunction "10_10") (pintype "passive"))
      (node (ref "SV2") (pin "9") (pinfunction "9_9") (pintype "passive"))
      (node (ref "U$2") (pin "H3") (pinfunction "H3_H3") (pintype "bidirectional"))
      (node (ref "U$3") (pin "P$5") (pinfunction "P$5_P$5") (pintype "bidirectional"))
    )
    (net (code "65") (name "Net-(SV2-Pad11)") (class "Default")
      (node (ref "SV2") (pin "11") (pinfunction "11_11") (pintype "passive"))
      (node (ref "SV2") (pin "12") (pinfunction "12_12") (pintype "passive"))
      (node (ref "U$2") (pin "H2") (pinfunction "H2_H2") (pintype "bidirectional"))
      (node (ref "U$3") (pin "P$6") (pinfunction "P$6_P$6") (pintype "bidirectional"))
    )
    (net (code "66") (name "Net-(SV2-Pad13)") (class "Default")
      (node (ref "SV2") (pin "13") (pinfunction "13_13") (pintype "passive"))
      (node (ref "SV2") (pin "14") (pinfunction "14_14") (pintype "passive"))
      (node (ref "U$2") (pin "H1") (pinfunction "H1_H1") (pintype "bidirectional"))
      (node (ref "U$3") (pin "P$7") (pinfunction "P$7_P$7") (pintype "bidirectional"))
    )
    (net (code "67") (name "Net-(U$6-S)") (class "Default")
      (node (ref "JP9") (pin "8") (pinfunction "8_8") (pintype "passive"))
      (node (ref "R32") (pin "1") (pinfunction "1_1") (pintype "passive"))
      (node (ref "U$6") (pin "SOURCE") (pinfunction "S_SOURCE") (pintype "passive"))
    )
    (net (code "68") (name "Net-(U$15-S)") (class "Default")
      (node (ref "JP9") (pin "7") (pinfunction "7_7") (pintype "passive"))
      (node (ref "R30") (pin "1") (pinfunction "1_1") (pintype "passive"))
      (node (ref "U$15") (pin "SOURCE") (pinfunction "S_SOURCE") (pintype "passive"))
    )
    (net (code "69") (name "VCC_Hall_1") (class "Default")
      (node (ref "SV1") (pin "15") (pinfunction "15_15") (pintype "passive"))
      (node (ref "SV1") (pin "16") (pinfunction "16_16") (pintype "passive"))
      (node (ref "U$1") (pin "VCC_HALL") (pinfunction "VCC_HALL_VCC_HALL") (pintype "bidirectional"))
      (node (ref "U$4") (pin "P$8") (pinfunction "P$8_P$8") (pintype "bidirectional"))
    )
    (net (code "70") (name "VCC_Hall_2") (class "Default")
      (node (ref "SV2") (pin "15") (pinfunction "15_15") (pintype "passive"))
      (node (ref "SV2") (pin "16") (pinfunction "16_16") (pintype "passive"))
      (node (ref "U$2") (pin "VCC_HALL") (pinfunction "VCC_HALL_VCC_HALL") (pintype "bidirectional"))
      (node (ref "U$3") (pin "P$8") (pinfunction "P$8_P$8") (pintype "bidirectional"))
    )
    (net (code "71") (name "unconnected-(DD2-D5-Pad14)") (class "Default")
      (node (ref "DD2") (pin "14") (pinfunction "D5_14") (pintype "bidirectional"))
    )
    (net (code "72") (name "unconnected-(DD2-D6-Pad13)") (class "Default")
      (node (ref "DD2") (pin "13") (pinfunction "D6_13") (pintype "bidirectional"))
    )
    (net (code "73") (name "unconnected-(DD2-D7-Pad12)") (class "Default")
      (node (ref "DD2") (pin "12") (pinfunction "D7_12") (pintype "bidirectional"))
    )
    (net (code "74") (name "unconnected-(DD2-D8-Pad11)") (class "Default")
      (node (ref "DD2") (pin "11") (pinfunction "D8_11") (pintype "bidirectional"))
    )
    (net (code "75") (name "unconnected-(DD2-S5-Pad7)") (class "Default")
      (node (ref "DD2") (pin "7") (pinfunction "S5_7") (pintype "bidirectional"))
    )
    (net (code "76") (name "unconnected-(DD2-S6-Pad8)") (class "Default")
      (node (ref "DD2") (pin "8") (pinfunction "S6_8") (pintype "bidirectional"))
    )
    (net (code "77") (name "unconnected-(DD2-S7-Pad9)") (class "Default")
      (node (ref "DD2") (pin "9") (pinfunction "S7_9") (pintype "bidirectional"))
    )
    (net (code "78") (name "unconnected-(DD2-S8-Pad10)") (class "Default")
      (node (ref "DD2") (pin "10") (pinfunction "S8_10") (pintype "bidirectional"))
    )
    (net (code "79") (name "unconnected-(IC3-IO6-Pad11)") (class "Default")
      (node (ref "IC3") (pin "11") (pinfunction "IO6_11") (pintype "bidirectional"))
    )
    (net (code "80") (name "unconnected-(IC3-IO7-Pad12)") (class "Default")
      (node (ref "IC3") (pin "12") (pinfunction "IO7_12") (pintype "bidirectional"))
    )
    (net (code "81") (name "unconnected-(IC3-~{INT}-Pad13)") (class "Default")
      (node (ref "IC3") (pin "13") (pinfunction "~{INT}_13") (pintype "open_collector"))
    )
    (net (code "82") (name "unconnected-(JP1-Pad1)") (class "Default")
      (node (ref "JP1") (pin "1") (pinfunction "1_1") (pintype "passive"))
    )
    (net (code "83") (name "unconnected-(JP1-Pad2)") (class "Default")
      (node (ref "JP1") (pin "2") (pinfunction "2_2") (pintype "passive"))
    )
    (net (code "84") (name "unconnected-(JP1-Pad3)") (class "Default")
      (node (ref "JP1") (pin "3") (pinfunction "3_3") (pintype "passive"))
    )
    (net (code "85") (name "unconnected-(JP1-Pad8)") (class "Default")
      (node (ref "JP1") (pin "8") (pinfunction "8_8") (pintype "passive"))
    )
    (net (code "86") (name "unconnected-(JP2-Pad1)") (class "Default")
      (node (ref "JP2") (pin "1") (pinfunction "1_1") (pintype "passive"))
    )
    (net (code "87") (name "unconnected-(JP2-Pad2)") (class "Default")
      (node (ref "JP2") (pin "2") (pinfunction "2_2") (pintype "passive"))
    )
    (net (code "88") (name "unconnected-(JP2-Pad3)") (class "Default")
      (node (ref "JP2") (pin "3") (pinfunction "3_3") (pintype "passive"))
    )
    (net (code "89") (name "unconnected-(JP2-Pad4)") (class "Default")
      (node (ref "JP2") (pin "4") (pinfunction "4_4") (pintype "passive"))
    )
    (net (code "90") (name "unconnected-(JP2-Pad5)") (class "Default")
      (node (ref "JP2") (pin "5") (pinfunction "5_5") (pintype "passive"))
    )
    (net (code "91") (name "unconnected-(JP2-Pad6)") (class "Default")
      (node (ref "JP2") (pin "6") (pinfunction "6_6") (pintype "passive"))
    )
    (net (code "92") (name "unconnected-(JP2-Pad7)") (class "Default")
      (node (ref "JP2") (pin "7") (pinfunction "7_7") (pintype "passive"))
    )
    (net (code "93") (name "unconnected-(JP2-Pad8)") (class "Default")
      (node (ref "JP2") (pin "8") (pinfunction "8_8") (pintype "passive"))
    )
    (net (code "94") (name "unconnected-(JP3-Pad10)") (class "Default")
      (node (ref "JP3") (pin "10") (pinfunction "10_10") (pintype "passive"))
    )
    (net (code "95") (name "unconnected-(JP3-Pad11)") (class "Default")
      (node (ref "JP3") (pin "11") (pinfunction "11_11") (pintype "passive"))
    )
    (net (code "96") (name "unconnected-(JP3-Pad12)") (class "Default")
      (node (ref "JP3") (pin "12") (pinfunction "12_12") (pintype "passive"))
    )
    (net (code "97") (name "unconnected-(JP3-Pad13)") (class "Default")
      (node (ref "JP3") (pin "13") (pinfunction "13_13") (pintype "passive"))
    )
    (net (code "98") (name "unconnected-(JP3-Pad14)") (class "Default")
      (node (ref "JP3") (pin "14") (pinfunction "14_14") (pintype "passive"))
    )
    (net (code "99") (name "unconnected-(JP3-Pad15)") (class "Default")
      (node (ref "JP3") (pin "15") (pinfunction "15_15") (pintype "passive"))
    )
    (net (code "100") (name "unconnected-(JP3-Pad16)") (class "Default")
      (node (ref "JP3") (pin "16") (pinfunction "16_16") (pintype "passive"))
    )
    (net (code "101") (name "unconnected-(JP3-Pad17)") (class "Default")
      (node (ref "JP3") (pin "17") (pinfunction "17_17") (pintype "passive"))
    )
    (net (code "102") (name "unconnected-(JP3-Pad18)") (class "Default")
      (node (ref "JP3") (pin "18") (pinfunction "18_18") (pintype "passive"))
    )
    (net (code "103") (name "unconnected-(JP3-Pad21)") (class "Default")
      (node (ref "JP3") (pin "21") (pinfunction "21_21") (pintype "passive"))
    )
    (net (code "104") (name "unconnected-(JP3-Pad22)") (class "Default")
      (node (ref "JP3") (pin "22") (pinfunction "22_22") (pintype "passive"))
    )
    (net (code "105") (name "unconnected-(JP3-Pad23)") (class "Default")
      (node (ref "JP3") (pin "23") (pinfunction "23_23") (pintype "passive"))
    )
    (net (code "106") (name "unconnected-(JP3-Pad24)") (class "Default")
      (node (ref "JP3") (pin "24") (pinfunction "24_24") (pintype "passive"))
    )
    (net (code "107") (name "unconnected-(JP3-Pad25)") (class "Default")
      (node (ref "JP3") (pin "25") (pinfunction "25_25") (pintype "passive"))
    )
    (net (code "108") (name "unconnected-(JP3-Pad26)") (class "Default")
      (node (ref "JP3") (pin "26") (pinfunction "26_26") (pintype "passive"))
    )
    (net (code "109") (name "unconnected-(JP3-Pad27)") (class "Default")
      (node (ref "JP3") (pin "27") (pinfunction "27_27") (pintype "passive"))
    )
    (net (code "110") (name "unconnected-(JP3-Pad28)") (class "Default")
      (node (ref "JP3") (pin "28") (pinfunction "28_28") (pintype "passive"))
    )
    (net (code "111") (name "unconnected-(JP3-Pad29)") (class "Default")
      (node (ref "JP3") (pin "29") (pinfunction "29_29") (pintype "passive"))
    )
    (net (code "112") (name "unconnected-(JP3-Pad30)") (class "Default")
      (node (ref "JP3") (pin "30") (pinfunction "30_30") (pintype "passive"))
    )
    (net (code "113") (name "unconnected-(JP3-Pad31)") (class "Default")
      (node (ref "JP3") (pin "31") (pinfunction "31_31") (pintype "passive"))
    )
    (net (code "114") (name "unconnected-(JP3-Pad32)") (class "Default")
      (node (ref "JP3") (pin "32") (pinfunction "32_32") (pintype "passive"))
    )
    (net (code "115") (name "unconnected-(JP3-Pad33)") (class "Default")
      (node (ref "JP3") (pin "33") (pinfunction "33_33") (pintype "passive"))
    )
    (net (code "116") (name "unconnected-(JP3-Pad34)") (class "Default")
      (node (ref "JP3") (pin "34") (pinfunction "34_34") (pintype "passive"))
    )
    (net (code "117") (name "unconnected-(JP4-Pad1)") (class "Default")
      (node (ref "JP4") (pin "1") (pinfunction "1_1") (pintype "passive"))
    )
    (net (code "118") (name "unconnected-(JP4-Pad2)") (class "Default")
      (node (ref "JP4") (pin "2") (pinfunction "2_2") (pintype "passive"))
    )
    (net (code "119") (name "unconnected-(JP4-Pad3)") (class "Default")
      (node (ref "JP4") (pin "3") (pinfunction "3_3") (pintype "passive"))
    )
    (net (code "120") (name "unconnected-(JP4-Pad4)") (class "Default")
      (node (ref "JP4") (pin "4") (pinfunction "4_4") (pintype "passive"))
    )
    (net (code "121") (name "unconnected-(JP4-Pad5)") (class "Default")
      (node (ref "JP4") (pin "5") (pinfunction "5_5") (pintype "passive"))
    )
    (net (code "122") (name "unconnected-(JP4-Pad6)") (class "Default")
      (node (ref "JP4") (pin "6") (pinfunction "6_6") (pintype "passive"))
    )
    (net (code "123") (name "unconnected-(JP4-Pad7)") (class "Default")
      (node (ref "JP4") (pin "7") (pinfunction "7_7") (pintype "passive"))
    )
    (net (code "124") (name "unconnected-(JP4-Pad8)") (class "Default")
      (node (ref "JP4") (pin "8") (pinfunction "8_8") (pintype "passive"))
    )
    (net (code "125") (name "unconnected-(JP4-Pad9)") (class "Default")
      (node (ref "JP4") (pin "9") (pinfunction "9_9") (pintype "passive"))
    )
    (net (code "126") (name "unconnected-(JP4-Pad10)") (class "Default")
      (node (ref "JP4") (pin "10") (pinfunction "10_10") (pintype "passive"))
    )
    (net (code "127") (name "unconnected-(JP5-Pad1)") (class "Default")
      (node (ref "JP5") (pin "1") (pinfunction "1_1") (pintype "passive"))
    )
    (net (code "128") (name "unconnected-(JP5-Pad2)") (class "Default")
      (node (ref "JP5") (pin "2") (pinfunction "2_2") (pintype "passive"))
    )
    (net (code "129") (name "unconnected-(JP5-Pad3)") (class "Default")
      (node (ref "JP5") (pin "3") (pinfunction "3_3") (pintype "passive"))
    )
    (net (code "130") (name "unconnected-(JP5-Pad4)") (class "Default")
      (node (ref "JP5") (pin "4") (pinfunction "4_4") (pintype "passive"))
    )
    (net (code "131") (name "unconnected-(JP5-Pad5)") (class "Default")
      (node (ref "JP5") (pin "5") (pinfunction "5_5") (pintype "passive"))
    )
    (net (code "132") (name "unconnected-(JP5-Pad6)") (class "Default")
      (node (ref "JP5") (pin "6") (pinfunction "6_6") (pintype "passive"))
    )
    (net (code "133") (name "unconnected-(JP5-Pad7)") (class "Default")
      (node (ref "JP5") (pin "7") (pinfunction "7_7") (pintype "passive"))
    )
    (net (code "134") (name "unconnected-(JP5-Pad8)") (class "Default")
      (node (ref "JP5") (pin "8") (pinfunction "8_8") (pintype "passive"))
    )
    (net (code "135") (name "unconnected-(JP8-Pad1)") (class "Default")
      (node (ref "JP8") (pin "1") (pinfunction "1_1") (pintype "passive"))
    )
    (net (code "136") (name "unconnected-(JP8-Pad2)") (class "Default")
      (node (ref "JP8") (pin "2") (pinfunction "2_2") (pintype "passive"))
    )
    (net (code "137") (name "unconnected-(JP8-Pad3)") (class "Default")
      (node (ref "JP8") (pin "3") (pinfunction "3_3") (pintype "passive"))
    )
    (net (code "138") (name "unconnected-(JP8-Pad4)") (class "Default")
      (node (ref "JP8") (pin "4") (pinfunction "4_4") (pintype "passive"))
    )
    (net (code "139") (name "unconnected-(JP8-Pad5)") (class "Default")
      (node (ref "JP8") (pin "5") (pinfunction "5_5") (pintype "passive"))
    )
    (net (code "140") (name "unconnected-(JP8-Pad6)") (class "Default")
      (node (ref "JP8") (pin "6") (pinfunction "6_6") (pintype "passive"))
    )
    (net (code "141") (name "unconnected-(JP8-Pad7)") (class "Default")
      (node (ref "JP8") (pin "7") (pinfunction "7_7") (pintype "passive"))
    )
    (net (code "142") (name "unconnected-(JP8-Pad8)") (class "Default")
      (node (ref "JP8") (pin "8") (pinfunction "8_8") (pintype "passive"))
    )
    (net (code "143") (name "unconnected-(JP9-Pad1)") (class "Default")
      (node (ref "JP9") (pin "1") (pinfunction "1_1") (pintype "passive"))
    )
    (net (code "144") (name "unconnected-(JP9-Pad2)") (class "Default")
      (node (ref "JP9") (pin "2") (pinfunction "2_2") (pintype "passive"))
    )
    (net (code "145") (name "unconnected-(JP9-Pad3)") (class "Default")
      (node (ref "JP9") (pin "3") (pinfunction "3_3") (pintype "passive"))
    )
    (net (code "146") (name "unconnected-(JP9-Pad4)") (class "Default")
      (node (ref "JP9") (pin "4") (pinfunction "4_4") (pintype "passive"))
    )
    (net (code "147") (name "unconnected-(JP9-Pad5)") (class "Default")
      (node (ref "JP9") (pin "5") (pinfunction "5_5") (pintype "passive"))
    )
    (net (code "148") (name "unconnected-(JP9-Pad6)") (class "Default")
      (node (ref "JP9") (pin "6") (pinfunction "6_6") (pintype "passive"))
    )
    (net (code "149") (name "unconnected-(U$1-PadN.C.)") (class "Default")
      (node (ref "U$1") (pin "N.C.") (pinfunction "N.C._N.C.") (pintype "bidirectional"))
    )
    (net (code "150") (name "unconnected-(U$2-PadN.C.)") (class "Default")
      (node (ref "U$2") (pin "N.C.") (pinfunction "N.C._N.C.") (pintype "bidirectional"))
    )
    (net (code "151") (name "unconnected-(U$5-PadREF_C)") (class "Default")
      (node (ref "U$5") (pin "REF_C") (pinfunction "REF_C_REF_C") (pintype "bidirectional"))
    )
    (net (code "152") (name "unconnected-(U$5-PadVOUT_C)") (class "Default")
      (node (ref "U$5") (pin "VOUT_C") (pinfunction "VOUT_C_VOUT_C") (pintype "bidirectional"))
    )
    (net (code "153") (name "unconnected-(U$5-PadVOUT_D)") (class "Default")
      (node (ref "U$5") (pin "VOUT_D") (pinfunction "VOUT_D_VOUT_D") (pintype "bidirectional"))
    )
    (net (code "154") (name "unconnected-(U$5-REF_D-PadVREF_D)") (class "Default")
      (node (ref "U$5") (pin "VREF_D") (pinfunction "REF_D_VREF_D") (pintype "bidirectional"))
    )
  )
)
